# LTC6362_Schematic_2.net
KiCad netlist of a schematic drawn in Altium Designer
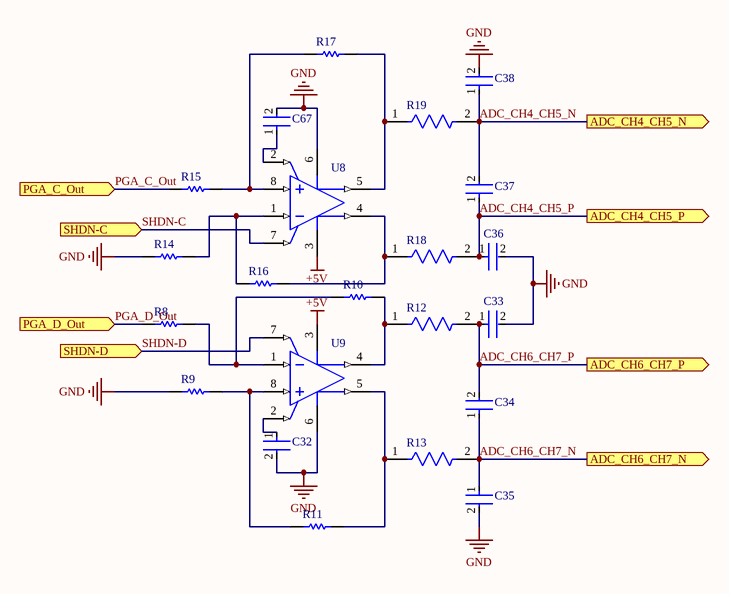
[diagram p0: LTC6362_Schematic_2.SchDoc]

(export (version "E")
  (design (tool "Eeschema 10.0.6"))
  (components
    (comp (ref "C32")
      (value "GQM1875C2ER10BB12D")
      (footprint "FP-GQM187-0_15-MFG")
      (description "Ceramic Capacitor 0.1pF ±0.1pF 250VDC C0G 0603 Paper T/R")
      (libsource (lib "Altium Content Vault") (part "02cd4be3c70576c341d710602a673aa"))
    )
    (comp (ref "C33")
      (value "CC0603KRX7R9BB392")
      (footprint "FP-CC0603-DA-MFG")
      (description "CAP CER 3900PF 50V X7R 0603")
      (fields (field (name "TOLERANCE") "10%") (field (name "VOLTAGE") "50V"))
      (libsource (lib "Altium Content Vault") (part "11868f565c42a9108669ba33697ecf6"))
    )
    (comp (ref "C34")
      (value "CC0603KRX7R9BB392")
      (footprint "FP-CC0603-DA-MFG")
      (description "CAP CER 3900PF 50V X7R 0603")
      (fields (field (name "TOLERANCE") "10%") (field (name "VOLTAGE") "50V"))
      (libsource (lib "Altium Content Vault") (part "11868f565c42a9108669ba33697ecf6"))
    )
    (comp (ref "C35")
      (value "CC0603KRX7R9BB392")
      (footprint "FP-CC0603-DA-MFG")
      (description "CAP CER 3900PF 50V X7R 0603")
      (fields (field (name "TOLERANCE") "10%") (field (name "VOLTAGE") "50V"))
      (libsource (lib "Altium Content Vault") (part "11868f565c42a9108669ba33697ecf6"))
    )
    (comp (ref "C36")
      (value "CC0603KRX7R9BB392")
      (footprint "FP-CC0603-DA-MFG")
      (description "CAP CER 3900PF 50V X7R 0603")
      (fields (field (name "TOLERANCE") "10%") (field (name "VOLTAGE") "50V"))
      (libsource (lib "Altium Content Vault") (part "11868f565c42a9108669ba33697ecf6"))
    )
    (comp (ref "C37")
      (value "CC0603KRX7R9BB392")
      (footprint "FP-CC0603-DA-MFG")
      (description "CAP CER 3900PF 50V X7R 0603")
      (fields (field (name "TOLERANCE") "10%") (field (name "VOLTAGE") "50V"))
      (libsource (lib "Altium Content Vault") (part "11868f565c42a9108669ba33697ecf6"))
    )
    (comp (ref "C38")
      (value "CC0603KRX7R9BB392")
      (footprint "FP-CC0603-DA-MFG")
      (description "CAP CER 3900PF 50V X7R 0603")
      (fields (field (name "TOLERANCE") "10%") (field (name "VOLTAGE") "50V"))
      (libsource (lib "Altium Content Vault") (part "11868f565c42a9108669ba33697ecf6"))
    )
    (comp (ref "C67")
      (value "GQM1875C2ER10BB12D")
      (footprint "FP-GQM187-0_15-MFG")
      (description "Ceramic Capacitor 0.1pF ±0.1pF 250VDC C0G 0603 Paper T/R")
      (libsource (lib "Altium Content Vault") (part "02cd4be3c70576c341d710602a673aa"))
    )
    (comp (ref "R8")
      (value "ERJ-6ENF1241V")
      (footprint "RESC2013X70X40LL20T20")
      (fields (field (name "MANUFACTURER") "Panasonic"))
      (libsource (lib "Altium Content Vault") (part "RES"))
    )
    (comp (ref "R9")
      (value "ERJ-6ENF1241V")
      (footprint "RESC2013X70X40LL20T20")
      (fields (field (name "MANUFACTURER") "Panasonic"))
      (libsource (lib "Altium Content Vault") (part "RES"))
    )
    (comp (ref "R10")
      (value "RC0805FR-071KL")
      (footprint "RESC2013X60X35ML10T20")
      (description "Chip Resistor, 1 KOhm, +/- 1%, 125 mW, -55 to 155 degC, 0805 (2012 Metric), RoHS, Tape and Reel")
      (fields (field (name "TOLERANCE") "1%") (field (name "MANUFACTURER") "Yageo"))
      (libsource (lib "Altium Content Vault") (part "RES-2"))
    )
    (comp (ref "R11")
      (value "RC0805FR-071KL")
      (footprint "RESC2013X60X35ML10T20")
      (description "Chip Resistor, 1 KOhm, +/- 1%, 125 mW, -55 to 155 degC, 0805 (2012 Metric), RoHS, Tape and Reel")
      (fields (field (name "TOLERANCE") "1%") (field (name "MANUFACTURER") "Yageo"))
      (libsource (lib "Altium Content Vault") (part "RES-2"))
    )
    (comp (ref "R12")
      (value "CRCW060335R7FKEA")
      (footprint "FP-CRCW0603-e3-IPC_B")
      (description "RES Thick Film, 35.7Ω, 1%, 0.1W, 100ppm/°C, 0603")
      (fields (field (name "TOLERANCE") "1%"))
      (libsource (lib "Altium Content Vault") (part "1029c3af85768c4190bb7ad29bc67b5"))
    )
    (comp (ref "R13")
      (value "CRCW060335R7FKEA")
      (footprint "FP-CRCW0603-e3-IPC_B")
      (description "RES Thick Film, 35.7Ω, 1%, 0.1W, 100ppm/°C, 0603")
      (fields (field (name "TOLERANCE") "1%"))
      (libsource (lib "Altium Content Vault") (part "1029c3af85768c4190bb7ad29bc67b5"))
    )
    (comp (ref "R14")
      (value "ERJ-6ENF1241V")
      (footprint "RESC2013X70X40LL20T20")
      (fields (field (name "MANUFACTURER") "Panasonic"))
      (libsource (lib "Altium Content Vault") (part "RES"))
    )
    (comp (ref "R15")
      (value "ERJ-6ENF1241V")
      (footprint "RESC2013X70X40LL20T20")
      (fields (field (name "MANUFACTURER") "Panasonic"))
      (libsource (lib "Altium Content Vault") (part "RES"))
    )
    (comp (ref "R16")
      (value "RC0805FR-071KL")
      (footprint "RESC2013X60X35ML10T20")
      (description "Chip Resistor, 1 KOhm, +/- 1%, 125 mW, -55 to 155 degC, 0805 (2012 Metric), RoHS, Tape and Reel")
      (fields (field (name "TOLERANCE") "1%") (field (name "MANUFACTURER") "Yageo"))
      (libsource (lib "Altium Content Vault") (part "RES-2"))
    )
    (comp (ref "R17")
      (value "RC0805FR-071KL")
      (footprint "RESC2013X60X35ML10T20")
      (description "Chip Resistor, 1 KOhm, +/- 1%, 125 mW, -55 to 155 degC, 0805 (2012 Metric), RoHS, Tape and Reel")
      (fields (field (name "TOLERANCE") "1%") (field (name "MANUFACTURER") "Yageo"))
      (libsource (lib "Altium Content Vault") (part "RES-2"))
    )
    (comp (ref "R18")
      (value "CRCW060335R7FKEA")
      (footprint "FP-CRCW0603-e3-IPC_B")
      (description "RES Thick Film, 35.7Ω, 1%, 0.1W, 100ppm/°C, 0603")
      (fields (field (name "TOLERANCE") "1%"))
      (libsource (lib "Altium Content Vault") (part "1029c3af85768c4190bb7ad29bc67b5"))
    )
    (comp (ref "R19")
      (value "CRCW060335R7FKEA")
      (footprint "FP-CRCW0603-e3-IPC_B")
      (description "RES Thick Film, 35.7Ω, 1%, 0.1W, 100ppm/°C, 0603")
      (fields (field (name "TOLERANCE") "1%"))
      (libsource (lib "Altium Content Vault") (part "1029c3af85768c4190bb7ad29bc67b5"))
    )
    (comp (ref "U8")
      (value "LTC6362HMS8#PBF")
      (footprint "LT-MS8-8_L")
      (fields
        (field (name "LINEAR TECHNOLOGY PART NUMBER") "LTC6362")
        (field (name "MANUFACTURER") "Linear Technology")
      )
      (libsource (lib "LTC6362HMS8_Symbol") (part "CMP-0359-00920-2"))
    )
    (comp (ref "U9")
      (value "LTC6362HMS8#PBF")
      (footprint "LT-MS8-8_L")
      (fields
        (field (name "LINEAR TECHNOLOGY PART NUMBER") "LTC6362")
        (field (name "MANUFACTURER") "Linear Technology")
      )
      (libsource (lib "LTC6362HMS8_Symbol") (part "CMP-0359-00920-2"))
    )
  )
  (nets
    (net (code "1") (name "+5V") (class "Default")
      (node (ref "U8") (pin "3") (pinfunction "V+_3") (pintype "power_in"))
      (node (ref "U9") (pin "3") (pinfunction "V+_3") (pintype "power_in"))
    )
    (net (code "2") (name "/ADC_CH4_CH5_N") (class "Default")
      (node (ref "C37") (pin "2") (pinfunction "2_2") (pintype "passive"))
      (node (ref "C38") (pin "1") (pinfunction "1_1") (pintype "passive"))
      (node (ref "R19") (pin "2") (pinfunction "2_2") (pintype "passive"))
    )
    (net (code "3") (name "/ADC_CH4_CH5_P") (class "Default")
      (node (ref "C36") (pin "1") (pinfunction "1_1") (pintype "passive"))
      (node (ref "C37") (pin "1") (pinfunction "1_1") (pintype "passive"))
      (node (ref "R18") (pin "2") (pinfunction "2_2") (pintype "passive"))
    )
    (net (code "4") (name "/ADC_CH6_CH7_N") (class "Default")
      (node (ref "C34") (pin "1") (pinfunction "1_1") (pintype "passive"))
      (node (ref "C35") (pin "1") (pinfunction "1_1") (pintype "passive"))
      (node (ref "R13") (pin "2") (pinfunction "2_2") (pintype "passive"))
    )
    (net (code "5") (name "/ADC_CH6_CH7_P") (class "Default")
      (node (ref "C33") (pin "1") (pinfunction "1_1") (pintype "passive"))
      (node (ref "C34") (pin "2") (pinfunction "2_2") (pintype "passive"))
      (node (ref "R12") (pin "2") (pinfunction "2_2") (pintype "passive"))
    )
    (net (code "6") (name "/PGA_C_Out") (class "Default")
      (node (ref "R15") (pin "1") (pinfunction "1_1") (pintype "passive"))
    )
    (net (code "7") (name "/PGA_D_Out") (class "Default")
      (node (ref "R8") (pin "1") (pinfunction "1_1") (pintype "passive"))
    )
    (net (code "8") (name "/SHDN-C") (class "Default")
      (node (ref "U8") (pin "7") (pinfunction "~{SHDN}_7") (pintype "input"))
    )
    (net (code "9") (name "/SHDN-D") (class "Default")
      (node (ref "U9") (pin "7") (pinfunction "~{SHDN}_7") (pintype "input"))
    )
    (net (code "10") (name "GND") (class "Default")
      (node (ref "C32") (pin "2") (pinfunction "2_2") (pintype "passive"))
      (node (ref "C33") (pin "2") (pinfunction "2_2") (pintype "passive"))
      (node (ref "C35") (pin "2") (pinfunction "2_2") (pintype "passive"))
      (node (ref "C36") (pin "2") (pinfunction "2_2") (pintype "passive"))
      (node (ref "C38") (pin "2") (pinfunction "2_2") (pintype "passive"))
      (node (ref "C67") (pin "2") (pinfunction "2_2") (pintype "passive"))
      (node (ref "R14") (pin "1") (pinfunction "1_1") (pintype "passive"))
      (node (ref "R9") (pin "1") (pinfunction "1_1") (pintype "passive"))
      (node (ref "U8") (pin "6") (pinfunction "V-_6") (pintype "power_in"))
      (node (ref "U9") (pin "6") (pinfunction "V-_6") (pintype "power_in"))
    )
    (net (code "11") (name "Net-(U8-+IN)") (class "Default")
      (node (ref "R15") (pin "2") (pinfunction "2_2") (pintype "passive"))
      (node (ref "R17") (pin "1") (pinfunction "1_1") (pintype "passive"))
      (node (ref "U8") (pin "8") (pinfunction "+IN_8") (pintype "input"))
    )
    (net (code "12") (name "Net-(U8-+OUT)") (class "Default")
      (node (ref "R16") (pin "2") (pinfunction "2_2") (pintype "passive"))
      (node (ref "R18") (pin "1") (pinfunction "1_1") (pintype "passive"))
      (node (ref "U8") (pin "4") (pinfunction "+OUT_4") (pintype "output"))
    )
    (net (code "13") (name "Net-(U8--IN)") (class "Default")
      (node (ref "R14") (pin "2") (pinfunction "2_2") (pintype "passive"))
      (node (ref "R16") (pin "1") (pinfunction "1_1") (pintype "passive"))
      (node (ref "U8") (pin "1") (pinfunction "-IN_1") (pintype "input"))
    )
    (net (code "14") (name "Net-(U8--OUT)") (class "Default")
      (node (ref "R17") (pin "2") (pinfunction "2_2") (pintype "passive"))
      (node (ref "R19") (pin "1") (pinfunction "1_1") (pintype "passive"))
      (node (ref "U8") (pin "5") (pinfunction "-OUT_5") (pintype "output"))
    )
    (net (code "15") (name "Net-(U8-VOCM)") (class "Default")
      (node (ref "C67") (pin "1") (pinfunction "1_1") (pintype "passive"))
      (node (ref "U8") (pin "2") (pinfunction "VOCM_2") (pintype "input"))
    )
    (net (code "16") (name "Net-(U9-+IN)") (class "Default")
      (node (ref "R11") (pin "1") (pinfunction "1_1") (pintype "passive"))
      (node (ref "R9") (pin "2") (pinfunction "2_2") (pintype "passive"))
      (node (ref "U9") (pin "8") (pinfunction "+IN_8") (pintype "input"))
    )
    (net (code "17") (name "Net-(U9-+OUT)") (class "Default")
      (node (ref "R10") (pin "2") (pinfunction "2_2") (pintype "passive"))
      (node (ref "R12") (pin "1") (pinfunction "1_1") (pintype "passive"))
      (node (ref "U9") (pin "4") (pinfunction "+OUT_4") (pintype "output"))
    )
    (net (code "18") (name "Net-(U9--IN)") (class "Default")
      (node (ref "R10") (pin "1") (pinfunction "1_1") (pintype "passive"))
      (node (ref "R8") (pin "2") (pinfunction "2_2") (pintype "passive"))
      (node (ref "U9") (pin "1") (pinfunction "-IN_1") (pintype "input"))
    )
    (net (code "19") (name "Net-(U9--OUT)") (class "Default")
      (node (ref "R11") (pin "2") (pinfunction "2_2") (pintype "passive"))
      (node (ref "R13") (pin "1") (pinfunction "1_1") (pintype "passive"))
      (node (ref "U9") (pin "5") (pinfunction "-OUT_5") (pintype "output"))
    )
    (net (code "20") (name "Net-(U9-VOCM)") (class "Default")
      (node (ref "C32") (pin "1") (pinfunction "1_1") (pintype "passive"))
      (node (ref "U9") (pin "2") (pinfunction "VOCM_2") (pintype "input"))
    )
  )
)
